# OpenBook_Schematic.net
KiCad netlist of a schematic drawn in EAGLE
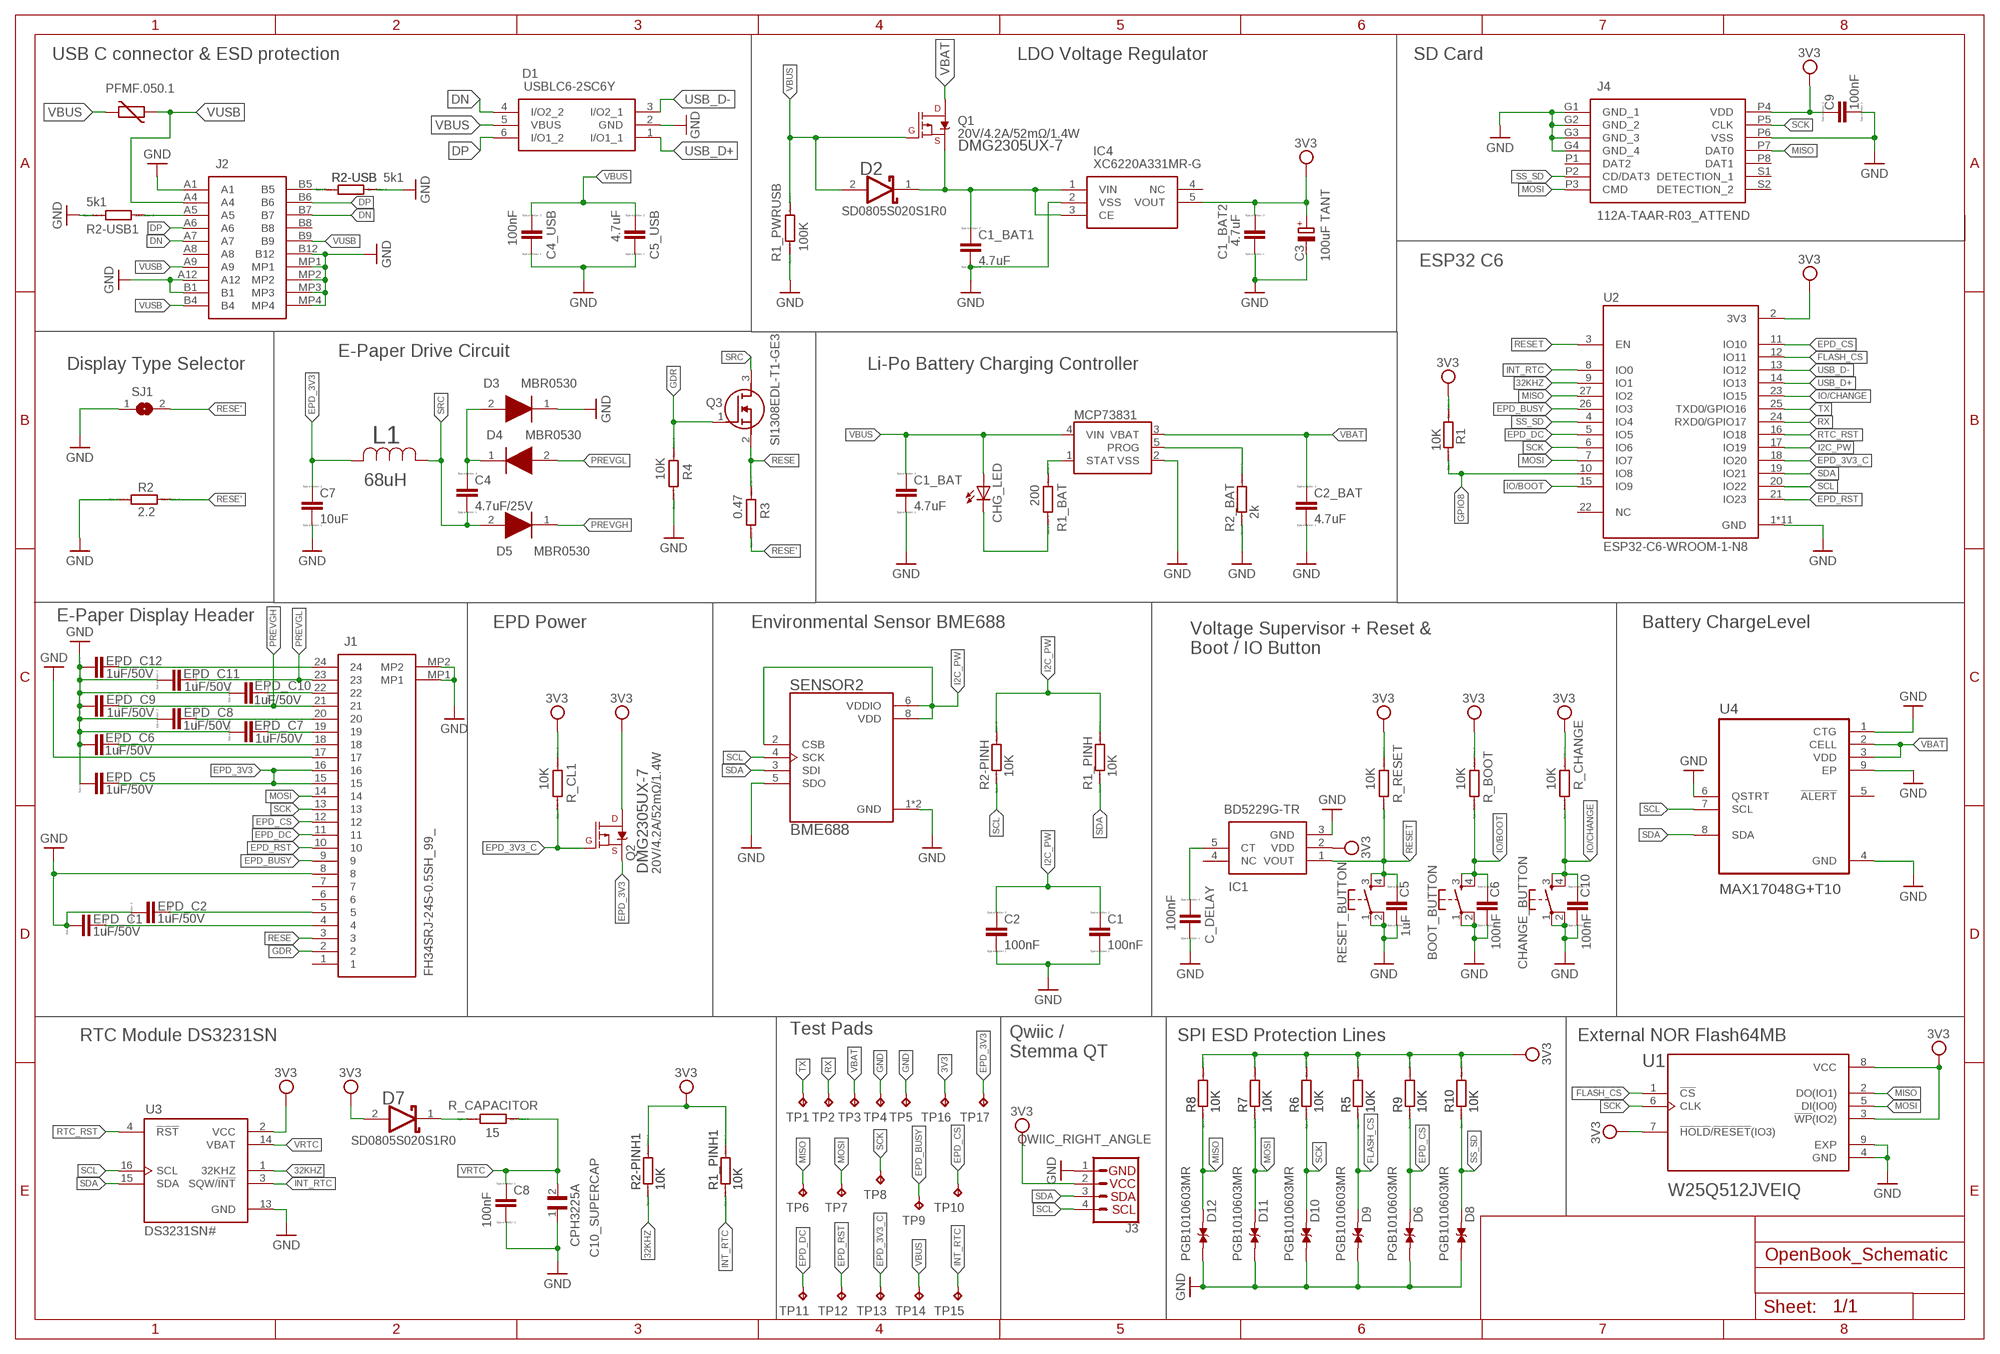
[diagram p0: schematic, sheet 1]

(export (version "E")
  (design (tool "Eeschema 10.0.6"))
  (components
    (comp (ref "BOOT_BUTTON")
      (value "BUTTON_CUSYOMV1")
      (footprint "eagle-import:MYBUTTON")
      (libsource (lib "eagle-import") (part "BUTTON_CUSYOMV1"))
    )
    (comp (ref "C1")
      (value "100nF")
      (footprint "eagle-import:EAGLE-LTSPICE_C0402")
      (libsource (lib "eagle-import") (part "EAGLE-LTSPICE_CC0402"))
    )
    (comp (ref "C1_BAT")
      (value "4.7uF")
      (footprint "eagle-import:EAGLE-LTSPICE_C0402")
      (libsource (lib "eagle-import") (part "EAGLE-LTSPICE_CC0402"))
    )
    (comp (ref "C1_BAT1")
      (value "4.7uF")
      (footprint "eagle-import:EAGLE-LTSPICE_C0402")
      (libsource (lib "eagle-import") (part "EAGLE-LTSPICE_CC0402"))
    )
    (comp (ref "C1_BAT2")
      (value "4.7uF")
      (footprint "eagle-import:EAGLE-LTSPICE_C0402")
      (libsource (lib "eagle-import") (part "EAGLE-LTSPICE_CC0402"))
    )
    (comp (ref "C2")
      (value "100nF")
      (footprint "eagle-import:EAGLE-LTSPICE_C0402")
      (libsource (lib "eagle-import") (part "EAGLE-LTSPICE_CC0402"))
    )
    (comp (ref "C2_BAT")
      (value "4.7uF")
      (footprint "eagle-import:EAGLE-LTSPICE_C0402")
      (libsource (lib "eagle-import") (part "EAGLE-LTSPICE_CC0402"))
    )
    (comp (ref "C3")
      (value "100uF TANT")
      (footprint "eagle-import:RCL_CT3528")
      (libsource (lib "eagle-import") (part "RCL_CPOL-EUCT3528"))
    )
    (comp (ref "C4")
      (value "4.7uF/25V")
      (footprint "eagle-import:EAGLE-LTSPICE_C0402")
      (libsource (lib "eagle-import") (part "EAGLE-LTSPICE_CC0402"))
    )
    (comp (ref "C4_USB")
      (value "100nF")
      (footprint "eagle-import:EAGLE-LTSPICE_C0402")
      (libsource (lib "eagle-import") (part "EAGLE-LTSPICE_CC0402"))
    )
    (comp (ref "C5")
      (value "1uF")
      (footprint "eagle-import:EAGLE-LTSPICE_C0402")
      (libsource (lib "eagle-import") (part "EAGLE-LTSPICE_CC0402"))
    )
    (comp (ref "C5_USB")
      (value "4.7uF")
      (footprint "eagle-import:EAGLE-LTSPICE_C0402")
      (libsource (lib "eagle-import") (part "EAGLE-LTSPICE_CC0402"))
    )
    (comp (ref "C6")
      (value "100nF")
      (footprint "eagle-import:EAGLE-LTSPICE_C0402")
      (libsource (lib "eagle-import") (part "EAGLE-LTSPICE_CC0402"))
    )
    (comp (ref "C7")
      (value "10uF")
      (footprint "eagle-import:EAGLE-LTSPICE_C0402")
      (libsource (lib "eagle-import") (part "EAGLE-LTSPICE_CC0402"))
    )
    (comp (ref "C8")
      (value "100nF")
      (footprint "eagle-import:EAGLE-LTSPICE_C0402")
      (libsource (lib "eagle-import") (part "EAGLE-LTSPICE_CC0402"))
    )
    (comp (ref "C9")
      (value "100nF")
      (footprint "eagle-import:EAGLE-LTSPICE_C0402")
      (libsource (lib "eagle-import") (part "EAGLE-LTSPICE_CC0402"))
    )
    (comp (ref "C10")
      (value "100nF")
      (footprint "eagle-import:EAGLE-LTSPICE_C0402")
      (libsource (lib "eagle-import") (part "EAGLE-LTSPICE_CC0402"))
    )
    (comp (ref "C10_SUPERCAP")
      (value "CPH3225A")
      (footprint "eagle-import:CAPCP3225X100N")
      (fields (field (name "MF") "Seiko Instruments"))
      (libsource (lib "eagle-import") (part "CPH3225A"))
    )
    (comp (ref "CHANGE_BUTTON")
      (value "BUTTON_CUSYOMV1")
      (footprint "eagle-import:MYBUTTON")
      (libsource (lib "eagle-import") (part "BUTTON_CUSYOMV1"))
    )
    (comp (ref "CHG_LED")
      (value "ADAFRUIT_LEDCHIP-LED0603")
      (footprint "eagle-import:ADAFRUIT_CHIP-LED0603")
      (libsource (lib "eagle-import") (part "ADAFRUIT_LEDCHIP-LED0603"))
    )
    (comp (ref "C_DELAY")
      (value "100nF")
      (footprint "eagle-import:EAGLE-LTSPICE_C0402")
      (libsource (lib "eagle-import") (part "EAGLE-LTSPICE_CC0402"))
    )
    (comp (ref "D1")
      (value "USBLC6-2SC6Y")
      (footprint "eagle-import:SOT95P280X145-6N")
      (fields (field (name "MF") "STMicroelectronics"))
      (libsource (lib "eagle-import") (part "USBLC6-2SC6Y"))
    )
    (comp (ref "D2")
      (value "ESP32_WROVER_AVX---SD0805S020S1R0_AVX_SD0805S020S1R0_0_0AVX_SD0805S020S1R0_0_0")
      (footprint "eagle-import:ESP32_WROVER_AVX---SD0805S020S1R0_AVX_SD0805S020S1R0_0")
      (fields
        (field (name "DIGIKEY_PART_NUMBER") "478-7800-1-ND")
        (field (name "MF") "AVX")
        (field (name "MOUSER_PART_NUMBER") "581-SD0805S020S1R0")
        (field (name "SD0805S020S1R0") "SD0805S020S1R0")
      )
      (libsource (lib "eagle-import") (part "ESP32_WROVER_AVX---SD0805S020S1R0_AVX_SD0805S020S1R0_0_0AVX_SD0805S020S1R0_0_0"))
    )
    (comp (ref "D3")
      (value "MBR0530")
      (footprint "eagle-import:SOD3716X135N")
      (fields (field (name "MF") "ON Semiconductor"))
      (libsource (lib "eagle-import") (part "MBR0530"))
    )
    (comp (ref "D4")
      (value "MBR0530")
      (footprint "eagle-import:SOD3716X135N")
      (fields (field (name "MF") "ON Semiconductor"))
      (libsource (lib "eagle-import") (part "MBR0530"))
    )
    (comp (ref "D5")
      (value "MBR0530")
      (footprint "eagle-import:SOD3716X135N")
      (fields (field (name "MF") "ON Semiconductor"))
      (libsource (lib "eagle-import") (part "MBR0530"))
    )
    (comp (ref "D6")
      (value "PGB1010603MR")
      (footprint "eagle-import:DIOC1608X36N")
      (fields (field (name "MF") "Littelfuse Inc."))
      (libsource (lib "eagle-import") (part "PGB1010603MR"))
    )
    (comp (ref "D7")
      (value "ESP32_WROVER_AVX---SD0805S020S1R0_AVX_SD0805S020S1R0_0_0AVX_SD0805S020S1R0_0_0")
      (footprint "eagle-import:ESP32_WROVER_AVX---SD0805S020S1R0_AVX_SD0805S020S1R0_0")
      (fields
        (field (name "DIGIKEY_PART_NUMBER") "478-7800-1-ND")
        (field (name "MF") "AVX")
        (field (name "MOUSER_PART_NUMBER") "581-SD0805S020S1R0")
        (field (name "DIODE") "SD0805S020S1R0")
      )
      (libsource (lib "eagle-import") (part "ESP32_WROVER_AVX---SD0805S020S1R0_AVX_SD0805S020S1R0_0_0AVX_SD0805S020S1R0_0_0"))
    )
    (comp (ref "D8")
      (value "PGB1010603MR")
      (footprint "eagle-import:DIOC1608X36N")
      (fields (field (name "MF") "Littelfuse Inc."))
      (libsource (lib "eagle-import") (part "PGB1010603MR"))
    )
    (comp (ref "D9")
      (value "PGB1010603MR")
      (footprint "eagle-import:DIOC1608X36N")
      (fields (field (name "MF") "Littelfuse Inc."))
      (libsource (lib "eagle-import") (part "PGB1010603MR"))
    )
    (comp (ref "D10")
      (value "PGB1010603MR")
      (footprint "eagle-import:DIOC1608X36N")
      (fields (field (name "MF") "Littelfuse Inc."))
      (libsource (lib "eagle-import") (part "PGB1010603MR"))
    )
    (comp (ref "D11")
      (value "PGB1010603MR")
      (footprint "eagle-import:DIOC1608X36N")
      (fields (field (name "MF") "Littelfuse Inc."))
      (libsource (lib "eagle-import") (part "PGB1010603MR"))
    )
    (comp (ref "D12")
      (value "PGB1010603MR")
      (footprint "eagle-import:DIOC1608X36N")
      (fields (field (name "MF") "Littelfuse Inc."))
      (libsource (lib "eagle-import") (part "PGB1010603MR"))
    )
    (comp (ref "EPD_C1")
      (value "1uF/50V")
      (footprint "eagle-import:EAGLE-LTSPICE_C0402")
      (libsource (lib "eagle-import") (part "EAGLE-LTSPICE_CC0402"))
    )
    (comp (ref "EPD_C2")
      (value "1uF/50V")
      (footprint "eagle-import:EAGLE-LTSPICE_C0402")
      (libsource (lib "eagle-import") (part "EAGLE-LTSPICE_CC0402"))
    )
    (comp (ref "EPD_C5")
      (value "1uF/50V")
      (footprint "eagle-import:EAGLE-LTSPICE_C0402")
      (libsource (lib "eagle-import") (part "EAGLE-LTSPICE_CC0402"))
    )
    (comp (ref "EPD_C6")
      (value "1uF/50V")
      (footprint "eagle-import:EAGLE-LTSPICE_C0402")
      (libsource (lib "eagle-import") (part "EAGLE-LTSPICE_CC0402"))
    )
    (comp (ref "EPD_C7")
      (value "1uF/50V")
      (footprint "eagle-import:EAGLE-LTSPICE_C0402")
      (libsource (lib "eagle-import") (part "EAGLE-LTSPICE_CC0402"))
    )
    (comp (ref "EPD_C8")
      (value "1uF/50V")
      (footprint "eagle-import:EAGLE-LTSPICE_C0402")
      (libsource (lib "eagle-import") (part "EAGLE-LTSPICE_CC0402"))
    )
    (comp (ref "EPD_C9")
      (value "1uF/50V")
      (footprint "eagle-import:EAGLE-LTSPICE_C0402")
      (libsource (lib "eagle-import") (part "EAGLE-LTSPICE_CC0402"))
    )
    (comp (ref "EPD_C10")
      (value "1uF/50V")
      (footprint "eagle-import:EAGLE-LTSPICE_C0402")
      (libsource (lib "eagle-import") (part "EAGLE-LTSPICE_CC0402"))
    )
    (comp (ref "EPD_C11")
      (value "1uF/50V")
      (footprint "eagle-import:EAGLE-LTSPICE_C0402")
      (libsource (lib "eagle-import") (part "EAGLE-LTSPICE_CC0402"))
    )
    (comp (ref "EPD_C12")
      (value "1uF/50V")
      (footprint "eagle-import:EAGLE-LTSPICE_C0402")
      (libsource (lib "eagle-import") (part "EAGLE-LTSPICE_CC0402"))
    )
    (comp (ref "IC1")
      (value "BD5229G-TR")
      (footprint "eagle-import:SOT95P280X125-5N")
      (fields (field (name "MOUSER_PART_NUMBER") "755-BD5229G-TR"))
      (libsource (lib "eagle-import") (part "BD5229G-TR"))
    )
    (comp (ref "IC4")
      (value "XC6220A331MR-G")
      (footprint "eagle-import:SOT95P280X120-5N")
      (fields (field (name "MOUSER_PART_NUMBER") "865-XC6220A331MR-G"))
      (libsource (lib "eagle-import") (part "XC6220A331MR-G"))
    )
    (comp (ref "J1")
      (value "FH34SRJ-24S-0.5SH_99_")
      (footprint "eagle-import:FH34SRJ24S05SH99")
      (fields
        (field (name "MANUFACTURER_PART_NUMBER") "FH34SRJ-24S-0.5SH(99)")
        (field (name "MOUSER_PART_NUMBER") "798-FH34SRJ24S05SH99")
      )
      (libsource (lib "eagle-import") (part "FH34SRJ-24S-0.5SH_99_"))
    )
    (comp (ref "J2")
      (value "SAMACSYS_PARTS_USB4110-GF-A")
      (footprint "eagle-import:SAMACSYS_PARTS_USB4110GFA")
      (fields
        (field (name "MANUFACTURER_PART_NUMBER") "USB4110-GF-A")
        (field (name "MOUSER_PART_NUMBER") "640-USB4110-GF-A")
      )
      (libsource (lib "eagle-import") (part "SAMACSYS_PARTS_USB4110-GF-A"))
    )
    (comp (ref "J3")
      (value "QWIIC_RIGHT_ANGLE")
      (footprint "eagle-import:JST04_1MM_RA")
      (libsource (lib "eagle-import") (part "QWIIC_CONNECTORJS-1MM"))
    )
    (comp (ref "J4")
      (value "112A-TAAR-R03_ATTEND")
      (footprint "eagle-import:112ATAARR03ATTEND")
      (fields (field (name "MANUFACTURER_PART_NUMBER") "112A-TAAR-R03 ATTEND"))
      (libsource (lib "eagle-import") (part "112A-TAAR-R03_ATTEND"))
    )
    (comp (ref "L1")
      (value "744043680IND_4828-WE-TPC_WRE")
      (footprint "eagle-import:IND_4828-WE-TPC_WRE")
      (fields
        (field (name "MANUFACTURER_PART_NUMBER") "744043680")
        (field (name "L1") "68uH")
        (field (name "COPYRIGHT") "Copyright (C) 2024 Ultra Librarian. All rights reserved.")
      )
      (libsource (lib "eagle-import") (part "744043680IND_4828-WE-TPC_WRE"))
    )
    (comp (ref "MCP73831")
      (value "ESP32_WROVER_SPARKFUN-IC-POWER_MCP73831")
      (footprint "eagle-import:ESP32_WROVER_SPARKFUN-IC-POWER_SOT23-5")
      (libsource (lib "eagle-import") (part "ESP32_WROVER_SPARKFUN-IC-POWER_MCP73831"))
    )
    (comp (ref "PFMF.050.1")
      (value "ESP32C6_VARISTORCN1812")
      (footprint "eagle-import:ESP32C6_VARISTOR_CT_CN1812")
      (libsource (lib "eagle-import") (part "ESP32C6_VARISTORCN1812"))
    )
    (comp (ref "Q1")
      (value "20V/4.2A/52mΩ/1.4W")
      (footprint "eagle-import:ESP32_WROVER_SPARKFUN-DISCRETESEMI_SOT23-3")
      (libsource (lib "eagle-import") (part "ESP32_WROVER_SPARKFUN-DISCRETESEMI_MOSFET_PCH-DMG2305UX-7"))
    )
    (comp (ref "Q2")
      (value "20V/4.2A/52mΩ/1.4W")
      (footprint "eagle-import:ESP32_WROVER_SPARKFUN-DISCRETESEMI_SOT23-3")
      (libsource (lib "eagle-import") (part "ESP32_WROVER_SPARKFUN-DISCRETESEMI_MOSFET_PCH-DMG2305UX-7"))
    )
    (comp (ref "Q3")
      (value "SI1308EDL-T1-GE3")
      (footprint "eagle-import:SOT65P210X110-3N")
      (fields (field (name "MF") "Vishay Siliconix"))
      (libsource (lib "eagle-import") (part "SI1308EDL-T1-GE3"))
    )
    (comp (ref "R1")
      (value "10K")
      (footprint "eagle-import:ESP32_WROVER_EAGLE-LTSPICE_R0402")
      (libsource (lib "eagle-import") (part "ESP32_WROVER_EAGLE-LTSPICE_RR0402"))
    )
    (comp (ref "R1_BAT")
      (value "200")
      (footprint "eagle-import:ESP32_WROVER_EAGLE-LTSPICE_R0402")
      (libsource (lib "eagle-import") (part "ESP32_WROVER_EAGLE-LTSPICE_RR0402"))
    )
    (comp (ref "R1_PINH")
      (value "10K")
      (footprint "eagle-import:ESP32_WROVER_EAGLE-LTSPICE_R0402")
      (libsource (lib "eagle-import") (part "ESP32_WROVER_EAGLE-LTSPICE_RR0402"))
    )
    (comp (ref "R1_PINH1")
      (value "10K")
      (footprint "eagle-import:ESP32_WROVER_EAGLE-LTSPICE_R0402")
      (libsource (lib "eagle-import") (part "ESP32_WROVER_EAGLE-LTSPICE_RR0402"))
    )
    (comp (ref "R1_PWRUSB")
      (value "100K")
      (footprint "eagle-import:ESP32_WROVER_EAGLE-LTSPICE_R0402")
      (libsource (lib "eagle-import") (part "ESP32_WROVER_EAGLE-LTSPICE_RR0402"))
    )
    (comp (ref "R2")
      (value "2.2")
      (footprint "eagle-import:ESP32_WROVER_EAGLE-LTSPICE_R0402")
      (libsource (lib "eagle-import") (part "ESP32_WROVER_EAGLE-LTSPICE_RR0402"))
    )
    (comp (ref "R2-PINH")
      (value "10K")
      (footprint "eagle-import:ESP32_WROVER_EAGLE-LTSPICE_R0402")
      (libsource (lib "eagle-import") (part "ESP32_WROVER_EAGLE-LTSPICE_RR0402"))
    )
    (comp (ref "R2-PINH1")
      (value "10K")
      (footprint "eagle-import:ESP32_WROVER_EAGLE-LTSPICE_R0402")
      (libsource (lib "eagle-import") (part "ESP32_WROVER_EAGLE-LTSPICE_RR0402"))
    )
    (comp (ref "R2-USB")
      (value "5k1")
      (footprint "eagle-import:ESP32_WROVER_EAGLE-LTSPICE_R0402")
      (libsource (lib "eagle-import") (part "ESP32_WROVER_EAGLE-LTSPICE_RR0402"))
    )
    (comp (ref "R2-USB1")
      (value "5k1")
      (footprint "eagle-import:ESP32_WROVER_EAGLE-LTSPICE_R0402")
      (libsource (lib "eagle-import") (part "ESP32_WROVER_EAGLE-LTSPICE_RR0402"))
    )
    (comp (ref "R2_BAT")
      (value "2k")
      (footprint "eagle-import:ESP32_WROVER_EAGLE-LTSPICE_R0402")
      (libsource (lib "eagle-import") (part "ESP32_WROVER_EAGLE-LTSPICE_RR0402"))
    )
    (comp (ref "R3")
      (value "0.47")
      (footprint "eagle-import:ESP32_WROVER_EAGLE-LTSPICE_R0402")
      (libsource (lib "eagle-import") (part "ESP32_WROVER_EAGLE-LTSPICE_RR0402"))
    )
    (comp (ref "R4")
      (value "10K")
      (footprint "eagle-import:ESP32_WROVER_EAGLE-LTSPICE_R0402")
      (libsource (lib "eagle-import") (part "ESP32_WROVER_EAGLE-LTSPICE_RR0402"))
    )
    (comp (ref "R5")
      (value "10K")
      (footprint "eagle-import:ESP32_WROVER_EAGLE-LTSPICE_R0402")
      (libsource (lib "eagle-import") (part "ESP32_WROVER_EAGLE-LTSPICE_RR0402"))
    )
    (comp (ref "R6")
      (value "10K")
      (footprint "eagle-import:ESP32_WROVER_EAGLE-LTSPICE_R0402")
      (libsource (lib "eagle-import") (part "ESP32_WROVER_EAGLE-LTSPICE_RR0402"))
    )
    (comp (ref "R7")
      (value "10K")
      (footprint "eagle-import:ESP32_WROVER_EAGLE-LTSPICE_R0402")
      (libsource (lib "eagle-import") (part "ESP32_WROVER_EAGLE-LTSPICE_RR0402"))
    )
    (comp (ref "R8")
      (value "10K")
      (footprint "eagle-import:ESP32_WROVER_EAGLE-LTSPICE_R0402")
      (libsource (lib "eagle-import") (part "ESP32_WROVER_EAGLE-LTSPICE_RR0402"))
    )
    (comp (ref "R9")
      (value "10K")
      (footprint "eagle-import:ESP32_WROVER_EAGLE-LTSPICE_R0402")
      (libsource (lib "eagle-import") (part "ESP32_WROVER_EAGLE-LTSPICE_RR0402"))
    )
    (comp (ref "R10")
      (value "10K")
      (footprint "eagle-import:ESP32_WROVER_EAGLE-LTSPICE_R0402")
      (libsource (lib "eagle-import") (part "ESP32_WROVER_EAGLE-LTSPICE_RR0402"))
    )
    (comp (ref "RESET_BUTTON")
      (value "BUTTON_CUSYOMV1")
      (footprint "eagle-import:MYBUTTON")
      (libsource (lib "eagle-import") (part "BUTTON_CUSYOMV1"))
    )
    (comp (ref "R_BOOT")
      (value "10K")
      (footprint "eagle-import:ESP32_WROVER_EAGLE-LTSPICE_R0402")
      (libsource (lib "eagle-import") (part "ESP32_WROVER_EAGLE-LTSPICE_RR0402"))
    )
    (comp (ref "R_CAPACITOR")
      (value "15")
      (footprint "eagle-import:ESP32_WROVER_EAGLE-LTSPICE_R0402")
      (libsource (lib "eagle-import") (part "ESP32_WROVER_EAGLE-LTSPICE_RR0402"))
    )
    (comp (ref "R_CHANGE")
      (value "10K")
      (footprint "eagle-import:ESP32_WROVER_EAGLE-LTSPICE_R0402")
      (libsource (lib "eagle-import") (part "ESP32_WROVER_EAGLE-LTSPICE_RR0402"))
    )
    (comp (ref "R_CL1")
      (value "10K")
      (footprint "eagle-import:ESP32_WROVER_EAGLE-LTSPICE_R0402")
      (libsource (lib "eagle-import") (part "ESP32_WROVER_EAGLE-LTSPICE_RR0402"))
    )
    (comp (ref "R_RESET")
      (value "10K")
      (footprint "eagle-import:ESP32_WROVER_EAGLE-LTSPICE_R0402")
      (libsource (lib "eagle-import") (part "ESP32_WROVER_EAGLE-LTSPICE_RR0402"))
    )
    (comp (ref "SENSOR2")
      (value "ESP32_WROVER_BME680_BME680")
      (footprint "eagle-import:ESP32_WROVER_BME680_PSON80P300X300X100-8N")
      (fields
        (field (name "MF") "Bosch Sensortec")
        (field (name "MP") "BME680")
        (field (name "MP1") "BME688")
      )
      (libsource (lib "eagle-import") (part "ESP32_WROVER_BME680_BME680"))
    )
    (comp (ref "SJ1") (value "SJ") (footprint "eagle-import:SJ") (libsource (lib "eagle-import") (part "SJ")))
    (comp (ref "TP1")
      (value "TPTP20R")
      (footprint "eagle-import:TP20R")
      (libsource (lib "eagle-import") (part "TPTP20R"))
    )
    (comp (ref "TP2")
      (value "TPTP20R")
      (footprint "eagle-import:TP20R")
      (libsource (lib "eagle-import") (part "TPTP20R"))
    )
    (comp (ref "TP3")
      (value "TPTP20R")
      (footprint "eagle-import:TP20R")
      (libsource (lib "eagle-import") (part "TPTP20R"))
    )
    (comp (ref "TP4")
      (value "TPTP20R")
      (footprint "eagle-import:TP20R")
      (libsource (lib "eagle-import") (part "TPTP20R"))
    )
    (comp (ref "TP5")
      (value "TPTP20R")
      (footprint "eagle-import:TP20R")
      (libsource (lib "eagle-import") (part "TPTP20R"))
    )
    (comp (ref "TP6")
      (value "TPTP20R")
      (footprint "eagle-import:TP20R")
      (libsource (lib "eagle-import") (part "TPTP20R"))
    )
    (comp (ref "TP7")
      (value "TPTP20R")
      (footprint "eagle-import:TP20R")
      (libsource (lib "eagle-import") (part "TPTP20R"))
    )
    (comp (ref "TP8")
      (value "TPTP20R")
      (footprint "eagle-import:TP20R")
      (libsource (lib "eagle-import") (part "TPTP20R"))
    )
    (comp (ref "TP9")
      (value "TPTP20R")
      (footprint "eagle-import:TP20R")
      (libsource (lib "eagle-import") (part "TPTP20R"))
    )
    (comp (ref "TP10")
      (value "TPTP20R")
      (footprint "eagle-import:TP20R")
      (libsource (lib "eagle-import") (part "TPTP20R"))
    )
    (comp (ref "TP11")
      (value "TPTP20R")
      (footprint "eagle-import:TP20R")
      (libsource (lib "eagle-import") (part "TPTP20R"))
    )
    (comp (ref "TP12")
      (value "TPTP20R")
      (footprint "eagle-import:TP20R")
      (libsource (lib "eagle-import") (part "TPTP20R"))
    )
    (comp (ref "TP13")
      (value "TPTP20R")
      (footprint "eagle-import:TP20R")
      (libsource (lib "eagle-import") (part "TPTP20R"))
    )
    (comp (ref "TP14")
      (value "TPTP20R")
      (footprint "eagle-import:TP20R")
      (libsource (lib "eagle-import") (part "TPTP20R"))
    )
    (comp (ref "TP15")
      (value "TPTP20R")
      (footprint "eagle-import:TP20R")
      (libsource (lib "eagle-import") (part "TPTP20R"))
    )
    (comp (ref "TP16")
      (value "TPTP20R")
      (footprint "eagle-import:TP20R")
      (libsource (lib "eagle-import") (part "TPTP20R"))
    )
    (comp (ref "TP17")
      (value "TPTP20R")
      (footprint "eagle-import:TP20R")
      (libsource (lib "eagle-import") (part "TPTP20R"))
    )
    (comp (ref "U1")
      (value "W25Q512JVEIQ")
      (footprint "eagle-import:SON127P600X800X80-9N")
      (fields (field (name "MF") "Winbond Electronics"))
      (libsource (lib "eagle-import") (part "W25Q512JVEIQ"))
    )
    (comp (ref "U2")
      (value "ESP32-C6-WROOM-1-N8")
      (footprint "eagle-import:XCVR_ESP32-C6-WROOM-1-N8")
      (fields (field (name "MF") "Espressif Systems"))
      (libsource (lib "eagle-import") (part "ESP32-C6-WROOM-1-N8"))
    )
    (comp (ref "U3")
      (value "DS3231SN#")
      (footprint "eagle-import:SOIC127P1032X265-16N")
      (fields (field (name "MF") "Analog Devices"))
      (libsource (lib "eagle-import") (part "DS3231SN#"))
    )
    (comp (ref "U4")
      (value "MAX17048G+T10")
      (footprint "eagle-import:SON50P200X200X80-9N")
      (fields (field (name "MF") "Analog Devices"))
      (libsource (lib "eagle-import") (part "MAX17048G+T10"))
    )
  )
  (nets
    (net (code "1") (name "3V3") (class "Default")
      (node (ref "C1_BAT2") (pin "2") (pinfunction "2_2") (pintype "passive"))
      (node (ref "C3") (pin "+") (pinfunction "+_+") (pintype "passive"))
      (node (ref "C9") (pin "2") (pinfunction "2_2") (pintype "passive"))
      (node (ref "D7") (pin "2") (pinfunction "ANODE_2") (pintype "bidirectional"))
      (node (ref "IC1") (pin "2") (pinfunction "VDD_2") (pintype "bidirectional"))
      (node (ref "IC4") (pin "5") (pinfunction "VOUT_5") (pintype "bidirectional"))
      (node (ref "J3") (pin "2") (pinfunction "2_2") (pintype "power_in"))
      (node (ref "J4") (pin "P4") (pinfunction "VDD_P4") (pintype "bidirectional"))
      (node (ref "Q2") (pin "3") (pinfunction "D_3") (pintype "bidirectional"))
      (node (ref "R1") (pin "1") (pinfunction "1_1") (pintype "passive"))
      (node (ref "R10") (pin "2") (pinfunction "2_2") (pintype "passive"))
      (node (ref "R1_PINH1") (pin "2") (pinfunction "2_2") (pintype "passive"))
      (node (ref "R2-PINH1") (pin "2") (pinfunction "2_2") (pintype "passive"))
      (node (ref "R5") (pin "2") (pinfunction "2_2") (pintype "passive"))
      (node (ref "R6") (pin "2") (pinfunction "2_2") (pintype "passive"))
      (node (ref "R7") (pin "2") (pinfunction "2_2") (pintype "passive"))
      (node (ref "R8") (pin "2") (pinfunction "2_2") (pintype "passive"))
      (node (ref "R9") (pin "2") (pinfunction "2_2") (pintype "passive"))
      (node (ref "R_BOOT") (pin "2") (pinfunction "2_2") (pintype "passive"))
      (node (ref "R_CHANGE") (pin "2") (pinfunction "2_2") (pintype "passive"))
      (node (ref "R_CL1") (pin "2") (pinfunction "2_2") (pintype "passive"))
      (node (ref "R_RESET") (pin "2") (pinfunction "2_2") (pintype "passive"))
      (node (ref "TP16") (pin "TP") (pinfunction "TP_TP") (pintype "input"))
      (node (ref "U1") (pin "3") (pinfunction "~{WP}(IO2)_3") (pintype "bidirectional"))
      (node (ref "U1") (pin "7") (pinfunction "~{HOLD}/~{RESET}(IO3)_7") (pintype "bidirectional"))
      (node (ref "U1") (pin "8") (pinfunction "VCC_8") (pintype "power_in"))
      (node (ref "U2") (pin "2") (pinfunction "3V3_2") (pintype "power_in"))
      (node (ref "U3") (pin "2") (pinfunction "VCC_2") (pintype "power_in"))
    )
    (net (code "2") (name "32KHZ") (class "Default")
      (node (ref "R2-PINH1") (pin "1") (pinfunction "1_1") (pintype "passive"))
      (node (ref "U2") (pin "9") (pinfunction "IO1_9") (pintype "bidirectional"))
      (node (ref "U3") (pin "1") (pinfunction "32KHZ_1") (pintype "output"))
    )
    (net (code "3") (name "DN") (class "Default")
      (node (ref "D1") (pin "4") (pinfunction "I/O2_2_4") (pintype "bidirectional"))
      (node (ref "J2") (pin "A7") (pinfunction "A7_A7") (pintype "bidirectional"))
      (node (ref "J2") (pin "B7") (pinfunction "B7_B7") (pintype "bidirectional"))
    )
    (net (code "4") (name "DP") (class "Default")
      (node (ref "D1") (pin "6") (pinfunction "I/O1_2_6") (pintype "bidirectional"))
      (node (ref "J2") (pin "A6") (pinfunction "A6_A6") (pintype "bidirectional"))
      (node (ref "J2") (pin "B6") (pinfunction "B6_B6") (pintype "bidirectional"))
    )
    (net (code "5") (name "EPD_3V3") (class "Default")
      (node (ref "C7") (pin "2") (pinfunction "2_2") (pintype "passive"))
      (node (ref "EPD_C5") (pin "1") (pinfunction "1_1") (pintype "passive"))
      (node (ref "J1") (pin "15") (pinfunction "15_15") (pintype "bidirectional"))
      (node (ref "J1") (pin "16") (pinfunction "16_16") (pintype "bidirectional"))
      (node (ref "L1") (pin "2") (pinfunction "2_2") (pintype "passive"))
      (node (ref "Q2") (pin "2") (pinfunction "S_2") (pintype "bidirectional"))
      (node (ref "TP17") (pin "TP") (pinfunction "TP_TP") (pintype "input"))
    )
    (net (code "6") (name "EPD_3V3_C") (class "Default")
      (node (ref "Q2") (pin "1") (pinfunction "G_1") (pintype "bidirectional"))
      (node (ref "R_CL1") (pin "1") (pinfunction "1_1") (pintype "passive"))
      (node (ref "TP13") (pin "TP") (pinfunction "TP_TP") (pintype "input"))
      (node (ref "U2") (pin "18") (pinfunction "IO20_18") (pintype "bidirectional"))
    )
    (net (code "7") (name "EPD_BUSY") (class "Default")
      (node (ref "J1") (pin "9") (pinfunction "9_9") (pintype "bidirectional"))
      (node (ref "TP9") (pin "TP") (pinfunction "TP_TP") (pintype "input"))
      (node (ref "U2") (pin "26") (pinfunction "IO3_26") (pintype "bidirectional"))
    )
    (net (code "8") (name "EPD_CS") (class "Default")
      (node (ref "D6") (pin "2") (pinfunction "2_2") (pintype "passive"))
      (node (ref "J1") (pin "12") (pinfunction "12_12") (pintype "bidirectional"))
      (node (ref "R9") (pin "1") (pinfunction "1_1") (pintype "passive"))
      (node (ref "TP10") (pin "TP") (pinfunction "TP_TP") (pintype "input"))
      (node (ref "U2") (pin "11") (pinfunction "IO10_11") (pintype "bidirectional"))
    )
    (net (code "9") (name "EPD_DC") (class "Default")
      (node (ref "J1") (pin "11") (pinfunction "11_11") (pintype "bidirectional"))
      (node (ref "TP11") (pin "TP") (pinfunction "TP_TP") (pintype "input"))
      (node (ref "U2") (pin "5") (pinfunction "IO5_5") (pintype "bidirectional"))
    )
    (net (code "10") (name "EPD_RST") (class "Default")
      (node (ref "J1") (pin "10") (pinfunction "10_10") (pintype "bidirectional"))
      (node (ref "TP12") (pin "TP") (pinfunction "TP_TP") (pintype "input"))
      (node (ref "U2") (pin "21") (pinfunction "IO23_21") (pintype "bidirectional"))
    )
    (net (code "11") (name "FLASH_CS") (class "Default")
      (node (ref "D9") (pin "2") (pinfunction "2_2") (pintype "passive"))
      (node (ref "R5") (pin "1") (pinfunction "1_1") (pintype "passive"))
      (node (ref "U1") (pin "1") (pinfunction "~{CS}_1") (pintype "input"))
      (node (ref "U2") (pin "12") (pinfunction "IO11_12") (pintype "bidirectional"))
    )
    (net (code "12") (name "GDR") (class "Default")
      (node (ref "J1") (pin "2") (pinfunction "2_2") (pintype "bidirectional"))
      (node (ref "Q3") (pin "1") (pinfunction "G_1") (pintype "bidirectional"))
      (node (ref "R4") (pin "2") (pinfunction "2_2") (pintype "passive"))
    )
    (net (code "13") (name "GND") (class "Default")
      (node (ref "BOOT_BUTTON") (pin "1") (pinfunction "1_1") (pintype "passive"))
      (node (ref "BOOT_BUTTON") (pin "2") (pinfunction "2_2") (pintype "passive"))
      (node (ref "C1") (pin "1") (pinfunction "1_1") (pintype "passive"))
      (node (ref "C10") (pin "1") (pinfunction "1_1") (pintype "passive"))
      (node (ref "C10_SUPERCAP") (pin "1") (pinfunction "1_1") (pintype "passive"))
      (node (ref "C1_BAT") (pin "1") (pinfunction "1_1") (pintype "passive"))
      (node (ref "C1_BAT1") (pin "1") (pinfunction "1_1") (pintype "passive"))
      (node (ref "C1_BAT2") (pin "1") (pinfunction "1_1") (pintype "passive"))
      (node (ref "C2") (pin "1") (pinfunction "1_1") (pintype "passive"))
      (node (ref "C2_BAT") (pin "1") (pinfunction "1_1") (pintype "passive"))
      (node (ref "C3") (pin "-") (pinfunction "-_-") (pintype "passive"))
      (node (ref "C4_USB") (pin "1") (pinfunction "1_1") (pintype "passive"))
      (node (ref "C5") (pin "1") (pinfunction "1_1") (pintype "passive"))
      (node (ref "C5_USB") (pin "1") (pinfunction "1_1") (pintype "passive"))
      (node (ref "C6") (pin "1") (pinfunction "1_1") (pintype "passive"))
      (node (ref "C7") (pin "1") (pinfunction "1_1") (pintype "passive"))
      (node (ref "C8") (pin "2") (pinfunction "2_2") (pintype "passive"))
      (node (ref "C9") (pin "1") (pinfunction "1_1") (pintype "passive"))
      (node (ref "CHANGE_BUTTON") (pin "1") (pinfunction "1_1") (pintype "passive"))
      (node (ref "CHANGE_BUTTON") (pin "2") (pinfunction "2_2") (pintype "passive"))
      (node (ref "C_DELAY") (pin "1") (pinfunction "1_1") (pintype "passive"))
      (node (ref "D1") (pin "2") (pinfunction "GND_2") (pintype "bidirectional"))
      (node (ref "D10") (pin "1") (pinfunction "1_1") (pintype "passive"))
      (node (ref "D11") (pin "1") (pinfunction "1_1") (pintype "passive"))
      (node (ref "D12") (pin "1") (pinfunction "1_1") (pintype "passive"))
      (node (ref "D3") (pin "1") (pinfunction "K_1") (pintype "bidirectional"))
      (node (ref "D6") (pin "1") (pinfunction "1_1") (pintype "passive"))
      (node (ref "D8") (pin "1") (pinfunction "1_1") (pintype "passive"))
      (node (ref "D9") (pin "1") (pinfunction "1_1") (pintype "passive"))
      (node (ref "EPD_C1") (pin "2") (pinfunction "2_2") (pintype "passive"))
      (node (ref "EPD_C10") (pin "2") (pinfunction "2_2") (pintype "passive"))
      (node (ref "EPD_C11") (pin "2") (pinfunction "2_2") (pintype "passive"))
      (node (ref "EPD_C12") (pin "2") (pinfunction "2_2") (pintype "passive"))
      (node (ref "EPD_C2") (pin "2") (pinfunction "2_2") (pintype "passive"))
      (node (ref "EPD_C5") (pin "2") (pinfunction "2_2") (pintype "passive"))
      (node (ref "EPD_C6") (pin "2") (pinfunction "2_2") (pintype "passive"))
      (node (ref "EPD_C7") (pin "2") (pinfunction "2_2") (pintype "passive"))
      (node (ref "EPD_C8") (pin "2") (pinfunction "2_2") (pintype "passive"))
      (node (ref "EPD_C9") (pin "2") (pinfunction "2_2") (pintype "passive"))
      (node (ref "IC1") (pin "3") (pinfunction "GND_3") (pintype "bidirectional"))
      (node (ref "IC4") (pin "2") (pinfunction "VSS_2") (pintype "bidirectional"))
      (node (ref "J1") (pin "17") (pinfunction "17_17") (pintype "bidirectional"))
      (node (ref "J1") (pin "8") (pinfunction "8_8") (pintype "bidirectional"))
      (node (ref "J1") (pin "MP1") (pinfunction "MP1_MP1") (pintype "bidirectional"))
      (node (ref "J1") (pin "MP2") (pinfunction "MP2_MP2") (pintype "bidirectional"))
      (node (ref "J2") (pin "A1") (pinfunction "A1_A1") (pintype "bidirectional"))
      (node (ref "J2") (pin "A12") (pinfunction "A12_A12") (pintype "bidirectional"))
      (node (ref "J2") (pin "B1") (pinfunction "B1_B1") (pintype "bidirectional"))
      (node (ref "J2") (pin "B12") (pinfunction "B12_B12") (pintype "bidirectional"))
      (node (ref "J2") (pin "MP1") (pinfunction "MP1_MP1") (pintype "bidirectional"))
      (node (ref "J2") (pin "MP2") (pinfunction "MP2_MP2") (pintype "bidirectional"))
      (node (ref "J2") (pin "MP3") (pinfunction "MP3_MP3") (pintype "bidirectional"))
      (node (ref "J2") (pin "MP4") (pinfunction "MP4_MP4") (pintype "bidirectional"))
      (node (ref "J3") (pin "1") (pinfunction "1_1") (pintype "power_in"))
      (node (ref "J4") (pin "G1") (pinfunction "GND_1_G1") (pintype "bidirectional"))
      (node (ref "J4") (pin "G2") (pinfunction "GND_2_G2") (pintype "bidirectional"))
      (node (ref "J4") (pin "G3") (pinfunction "GND_3_G3") (pintype "bidirectional"))
      (node (ref "J4") (pin "G4") (pinfunction "GND_4_G4") (pintype "bidirectional"))
      (node (ref "J4") (pin "P6") (pinfunction "VSS_P6") (pintype "bidirectional"))
      (node (ref "MCP73831") (pin "2") (pinfunction "VSS_2") (pintype "power_in"))
      (node (ref "R1_PWRUSB") (pin "2") (pinfunction "2_2") (pintype "passive"))
      (node (ref "R2") (pin "1") (pinfunction "1_1") (pintype "passive"))
      (node (ref "R2-USB") (pin "2") (pinfunction "2_2") (pintype "passive"))
      (node (ref "R2-USB1") (pin "1") (pinfunction "1_1") (pintype "passive"))
      (node (ref "R2_BAT") (pin "1") (pinfunction "1_1") (pintype "passive"))
      (node (ref "R4") (pin "1") (pinfunction "1_1") (pintype "passive"))
      (node (ref "RESET_BUTTON") (pin "1") (pinfunction "1_1") (pintype "passive"))
      (node (ref "RESET_BUTTON") (pin "2") (pinfunction "2_2") (pintype "passive"))
      (node (ref "SENSOR2") (pin "1") (pinfunction "GND_1") (pintype "power_in"))
      (node (ref "SENSOR2") (pin "5") (pinfunction "SDO_5") (pintype "bidirectional"))
      (node (ref "SENSOR2") (pin "7") (pinfunction "GND_7") (pintype "power_in"))
      (node (ref "SJ1") (pin "1") (pinfunction "1_1") (pintype "passive"))
      (node (ref "TP4") (pin "TP") (pinfunction "TP_TP") (pintype "input"))
      (node (ref "TP5") (pin "TP") (pinfunction "TP_TP") (pintype "input"))
      (node (ref "U1") (pin "4") (pinfunction "GND_4") (pintype "power_in"))
      (node (ref "U1") (pin "9") (pinfunction "EXP_9") (pintype "passive"))
      (node (ref "U2") (pin "1") (pinfunction "GND_1") (pintype "power_in"))
      (node (ref "U2") (pin "28") (pinfunction "GND_28") (pintype "power_in"))
      (node (ref "U2") (pin "29_1") (pinfunction "GND_29_1") (pintype "power_in"))
      (node (ref "U2") (pin "29_2") (pinfunction "GND_29_2") (pintype "power_in"))
      (node (ref "U2") (pin "29_3") (pinfunction "GND_29_3") (pintype "power_in"))
      (node (ref "U2") (pin "29_4") (pinfunction "GND_29_4") (pintype "power_in"))
      (node (ref "U2") (pin "29_5") (pinfunction "GND_29_5") (pintype "power_in"))
      (node (ref "U2") (pin "29_6") (pinfunction "GND_29_6") (pintype "power_in"))
      (node (ref "U2") (pin "29_7") (pinfunction "GND_29_7") (pintype "power_in"))
      (node (ref "U2") (pin "29_8") (pinfunction "GND_29_8") (pintype "power_in"))
      (node (ref "U2") (pin "29_9") (pinfunction "GND_29_9") (pintype "power_in"))
      (node (ref "U3") (pin "13") (pinfunction "GND_13") (pintype "power_in"))
      (node (ref "U4") (pin "1") (pinfunction "CTG_1") (pintype "power_in"))
      (node (ref "U4") (pin "4") (pinfunction "GND_4") (pintype "power_in"))
      (node (ref "U4") (pin "6") (pinfunction "QSTRT_6") (pintype "input"))
      (node (ref "U4") (pin "9") (pinfunction "EP_9") (pintype "power_in"))
    )
    (net (code "14") (name "GPIO8") (class "Default")
      (node (ref "R1") (pin "2") (pinfunction "2_2") (pintype "passive"))
      (node (ref "U2") (pin "10") (pinfunction "IO8_10") (pintype "bidirectional"))
    )
    (net (code "15") (name "I2C_PW") (class "Default")
      (node (ref "C1") (pin "2") (pinfunction "2_2") (pintype "passive"))
      (node (ref "C2") (pin "2") (pinfunction "2_2") (pintype "passive"))
      (node (ref "R1_PINH") (pin "2") (pinfunction "2_2") (pintype "passive"))
      (node (ref "R2-PINH") (pin "2") (pinfunction "2_2") (pintype "passive"))
      (node (ref "SENSOR2") (pin "2") (pinfunction "CSB_2") (pintype "input"))
      (node (ref "SENSOR2") (pin "6") (pinfunction "VDDIO_6") (pintype "power_in"))
      (node (ref "SENSOR2") (pin "8") (pinfunction "VDD_8") (pintype "power_in"))
      (node (ref "U2") (pin "17") (pinfunction "IO19_17") (pintype "bidirectional"))
    )
    (net (code "16") (name "INT_RTC") (class "Default")
      (node (ref "R1_PINH1") (pin "1") (pinfunction "1_1") (pintype "passive"))
      (node (ref "TP15") (pin "TP") (pinfunction "TP_TP") (pintype "input"))
      (node (ref "U2") (pin "8") (pinfunction "IO0_8") (pintype "bidirectional"))
      (node (ref "U3") (pin "3") (pinfunction "SQW/~{INT}_3") (pintype "output"))
    )
    (net (code "17") (name "IO{slash}BOOT") (class "Default")
      (node (ref "BOOT_BUTTON") (pin "3") (pinfunction "3_3") (pintype "passive"))
      (node (ref "BOOT_BUTTON") (pin "4") (pinfunction "4_4") (pintype "passive"))
      (node (ref "C6") (pin "2") (pinfunction "2_2") (pintype "passive"))
      (node (ref "R_BOOT") (pin "1") (pinfunction "1_1") (pintype "passive"))
      (node (ref "U2") (pin "15") (pinfunction "IO9_15") (pintype "bidirectional"))
    )
    (net (code "18") (name "IO{slash}CHANGE") (class "Default")
      (node (ref "C10") (pin "2") (pinfunction "2_2") (pintype "passive"))
      (node (ref "CHANGE_BUTTON") (pin "3") (pinfunction "3_3") (pintype "passive"))
      (node (ref "CHANGE_BUTTON") (pin "4") (pinfunction "4_4") (pintype "passive"))
      (node (ref "R_CHANGE") (pin "1") (pinfunction "1_1") (pintype "passive"))
      (node (ref "U2") (pin "23") (pinfunction "IO15_23") (pintype "bidirectional"))
    )
    (net (code "19") (name "MISO") (class "Default")
      (node (ref "D12") (pin "2") (pinfunction "2_2") (pintype "passive"))
      (node (ref "J4") (pin "P7") (pinfunction "DAT0_P7") (pintype "bidirectional"))
      (node (ref "R8") (pin "1") (pinfunction "1_1") (pintype "passive"))
      (node (ref "TP6") (pin "TP") (pinfunction "TP_TP") (pintype "input"))
      (node (ref "U1") (pin "2") (pinfunction "DO(IO1)_2") (pintype "bidirectional"))
      (node (ref "U2") (pin "27") (pinfunction "IO2_27") (pintype "bidirectional"))
    )
    (net (code "20") (name "MOSI") (class "Default")
      (node (ref "D11") (pin "2") (pinfunction "2_2") (pintype "passive"))
      (node (ref "J1") (pin "14") (pinfunction "14_14") (pintype "bidirectional"))
      (node (ref "J4") (pin "P3") (pinfunction "CMD_P3") (pintype "bidirectional"))
      (node (ref "R7") (pin "1") (pinfunction "1_1") (pintype "passive"))
      (node (ref "TP7") (pin "TP") (pinfunction "TP_TP") (pintype "input"))
      (node (ref "U1") (pin "5") (pinfunction "DI(IO0)_5") (pintype "bidirectional"))
      (node (ref "U2") (pin "7") (pinfunction "IO7_7") (pintype "bidirectional"))
    )
    (net (code "21") (name "Net-(CHG_LED-PadC)") (class "Default")
      (node (ref "CHG_LED") (pin "C") (pinfunction "C_C") (pintype "passive"))
      (node (ref "R1_BAT") (pin "1") (pinfunction "1_1") (pintype "passive"))
    )
    (net (code "22") (name "Net-(D2-CATHODE)") (class "Default")
      (node (ref "C1_BAT1") (pin "2") (pinfunction "2_2") (pintype "passive"))
      (node (ref "D2") (pin "1") (pinfunction "CATHODE_1") (pintype "bidirectional"))
      (node (ref "IC4") (pin "1") (pinfunction "VIN_1") (pintype "bidirectional"))
      (node (ref "IC4") (pin "3") (pinfunction "CE_3") (pintype "bidirectional"))
      (node (ref "Q1") (pin "2") (pinfunction "S_2") (pintype "bidirectional"))
    )
    (net (code "23") (name "Net-(D3-A)") (class "Default")
      (node (ref "C4") (pin "2") (pinfunction "2_2") (pintype "passive"))
      (node (ref "D3") (pin "2") (pinfunction "A_2") (pintype "bidirectional"))
      (node (ref "D4") (pin "1") (pinfunction "K_1") (pintype "bidirectional"))
    )
    (net (code "24") (name "Net-(D7-CATHODE)") (class "Default")
      (node (ref "D7") (pin "1") (pinfunction "CATHODE_1") (pintype "bidirectional"))
      (node (ref "R_CAPACITOR") (pin "2") (pinfunction "2_2") (pintype "passive"))
    )
    (net (code "25") (name "Net-(EPD_C1-Pad1)") (class "Default")
      (node (ref "EPD_C1") (pin "1") (pinfunction "1_1") (pintype "passive"))
      (node (ref "J1") (pin "4") (pinfunction "4_4") (pintype "bidirectional"))
    )
    (net (code "26") (name "Net-(EPD_C2-Pad1)") (class "Default")
      (node (ref "EPD_C2") (pin "1") (pinfunction "1_1") (pintype "passive"))
      (node (ref "J1") (pin "5") (pinfunction "5_5") (pintype "bidirectional"))
    )
    (net (code "27") (name "Net-(EPD_C6-Pad1)") (class "Default")
      (node (ref "EPD_C6") (pin "1") (pinfunction "1_1") (pintype "passive"))
      (node (ref "J1") (pin "18") (pinfunction "18_18") (pintype "bidirectional"))
    )
    (net (code "28") (name "Net-(EPD_C7-Pad1)") (class "Default")
      (node (ref "EPD_C7") (pin "1") (pinfunction "1_1") (pintype "passive"))
      (node (ref "J1") (pin "19") (pinfunction "19_19") (pintype "bidirectional"))
    )
    (net (code "29") (name "Net-(EPD_C8-Pad1)") (class "Default")
      (node (ref "EPD_C8") (pin "1") (pinfunction "1_1") (pintype "passive"))
      (node (ref "J1") (pin "20") (pinfunction "20_20") (pintype "bidirectional"))
    )
    (net (code "30") (name "Net-(EPD_C10-Pad1)") (class "Default")
      (node (ref "EPD_C10") (pin "1") (pinfunction "1_1") (pintype "passive"))
      (node (ref "J1") (pin "22") (pinfunction "22_22") (pintype "bidirectional"))
    )
    (net (code "31") (name "Net-(EPD_C12-Pad1)") (class "Default")
      (node (ref "EPD_C12") (pin "1") (pinfunction "1_1") (pintype "passive"))
      (node (ref "J1") (pin "24") (pinfunction "24_24") (pintype "bidirectional"))
    )
    (net (code "32") (name "Net-(IC1-CT)") (class "Default")
      (node (ref "C_DELAY") (pin "2") (pinfunction "2_2") (pintype "passive"))
      (node (ref "IC1") (pin "5") (pinfunction "CT_5") (pintype "bidirectional"))
    )
    (net (code "33") (name "Net-(J2-PadA5)") (class "Default")
      (node (ref "J2") (pin "A5") (pinfunction "A5_A5") (pintype "bidirectional"))
      (node (ref "R2-USB1") (pin "2") (pinfunction "2_2") (pintype "passive"))
    )
    (net (code "34") (name "Net-(J2-PadB5)") (class "Default")
      (node (ref "J2") (pin "B5") (pinfunction "B5_B5") (pintype "bidirectional"))
      (node (ref "R2-USB") (pin "1") (pinfunction "1_1") (pintype "passive"))
    )
    (net (code "35") (name "Net-(MCP73831-PROG)") (class "Default")
      (node (ref "MCP73831") (pin "5") (pinfunction "PROG_5") (pintype "input"))
      (node (ref "R2_BAT") (pin "2") (pinfunction "2_2") (pintype "passive"))
    )
    (net (code "36") (name "Net-(MCP73831-STAT)") (class "Default")
      (node (ref "MCP73831") (pin "1") (pinfunction "STAT_1") (pintype "output"))
      (node (ref "R1_BAT") (pin "2") (pinfunction "2_2") (pintype "passive"))
    )
    (net (code "37") (name "PREVGH") (class "Default")
      (node (ref "D5") (pin "1") (pinfunction "K_1") (pintype "bidirectional"))
      (node (ref "EPD_C9") (pin "1") (pinfunction "1_1") (pintype "passive"))
      (node (ref "J1") (pin "21") (pinfunction "21_21") (pintype "bidirectional"))
    )
    (net (code "38") (name "PREVGL") (class "Default")
      (node (ref "D4") (pin "2") (pinfunction "A_2") (pintype "bidirectional"))
      (node (ref "EPD_C11") (pin "1") (pinfunction "1_1") (pintype "passive"))
      (node (ref "J1") (pin "23") (pinfunction "23_23") (pintype "bidirectional"))
    )
    (net (code "39") (name "RESE") (class "Default")
      (node (ref "J1") (pin "3") (pinfunction "3_3") (pintype "bidirectional"))
      (node (ref "Q3") (pin "2") (pinfunction "S_2") (pintype "bidirectional"))
      (node (ref "R3") (pin "2") (pinfunction "2_2") (pintype "passive"))
    )
    (net (code "40") (name "RESE'") (class "Default")
      (node (ref "R2") (pin "2") (pinfunction "2_2") (pintype "passive"))
      (node (ref "R3") (pin "1") (pinfunction "1_1") (pintype "passive"))
      (node (ref "SJ1") (pin "2") (pinfunction "2_2") (pintype "passive"))
    )
    (net (code "41") (name "RESET") (class "Default")
      (node (ref "C5") (pin "2") (pinfunction "2_2") (pintype "passive"))
      (node (ref "IC1") (pin "1") (pinfunction "VOUT_1") (pintype "bidirectional"))
      (node (ref "RESET_BUTTON") (pin "3") (pinfunction "3_3") (pintype "passive"))
      (node (ref "RESET_BUTTON") (pin "4") (pinfunction "4_4") (pintype "passive"))
      (node (ref "R_RESET") (pin "1") (pinfunction "1_1") (pintype "passive"))
      (node (ref "U2") (pin "3") (pinfunction "EN_3") (pintype "input"))
    )
    (net (code "42") (name "RTC_RST") (class "Default")
      (node (ref "U2") (pin "16") (pinfunction "IO18_16") (pintype "bidirectional"))
      (node (ref "U3") (pin "4") (pinfunction "~{RST}_4") (pintype "input"))
    )
    (net (code "43") (name "RX") (class "Default")
      (node (ref "TP2") (pin "TP") (pinfunction "TP_TP") (pintype "input"))
      (node (ref "U2") (pin "24") (pinfunction "RXD0/GPIO17_24") (pintype "bidirectional"))
    )
    (net (code "44") (name "SCK") (class "Default")
      (node (ref "D10") (pin "2") (pinfunction "2_2") (pintype "passive"))
      (node (ref "J1") (pin "13") (pinfunction "13_13") (pintype "bidirectional"))
      (node (ref "J4") (pin "P5") (pinfunction "CLK_P5") (pintype "bidirectional"))
      (node (ref "R6") (pin "1") (pinfunction "1_1") (pintype "passive"))
      (node (ref "TP8") (pin "TP") (pinfunction "TP_TP") (pintype "input"))
      (node (ref "U1") (pin "6") (pinfunction "CLK_6") (pintype "input"))
      (node (ref "U2") (pin "6") (pinfunction "IO6_6") (pintype "bidirectional"))
    )
    (net (code "45") (name "SCL") (class "Default")
      (node (ref "J3") (pin "4") (pinfunction "4_4") (pintype "passive"))
      (node (ref "R2-PINH") (pin "1") (pinfunction "1_1") (pintype "passive"))
      (node (ref "SENSOR2") (pin "4") (pinfunction "SCK_4") (pintype "input"))
      (node (ref "U2") (pin "20") (pinfunction "IO22_20") (pintype "bidirectional"))
      (node (ref "U3") (pin "16") (pinfunction "SCL_16") (pintype "input"))
      (node (ref "U4") (pin "7") (pinfunction "SCL_7") (pintype "input"))
    )
    (net (code "46") (name "SDA") (class "Default")
      (node (ref "J3") (pin "3") (pinfunction "3_3") (pintype "passive"))
      (node (ref "R1_PINH") (pin "1") (pinfunction "1_1") (pintype "passive"))
      (node (ref "SENSOR2") (pin "3") (pinfunction "SDI_3") (pintype "bidirectional"))
      (node (ref "U2") (pin "19") (pinfunction "IO21_19") (pintype "bidirectional"))
      (node (ref "U3") (pin "15") (pinfunction "SDA_15") (pintype "bidirectional"))
      (node (ref "U4") (pin "8") (pinfunction "SDA_8") (pintype "bidirectional"))
    )
    (net (code "47") (name "SRC") (class "Default")
      (node (ref "C4") (pin "1") (pinfunction "1_1") (pintype "passive"))
      (node (ref "D5") (pin "2") (pinfunction "A_2") (pintype "bidirectional"))
      (node (ref "L1") (pin "1") (pinfunction "1_1") (pintype "passive"))
      (node (ref "Q3") (pin "3") (pinfunction "D_3") (pintype "bidirectional"))
    )
    (net (code "48") (name "SS_SD") (class "Default")
      (node (ref "D8") (pin "2") (pinfunction "2_2") (pintype "passive"))
      (node (ref "J4") (pin "P2") (pinfunction "CD/DAT3_P2") (pintype "bidirectional"))
      (node (ref "R10") (pin "1") (pinfunction "1_1") (pintype "passive"))
      (node (ref "U2") (pin "4") (pinfunction "IO4_4") (pintype "bidirectional"))
    )
    (net (code "49") (name "TX") (class "Default")
      (node (ref "TP1") (pin "TP") (pinfunction "TP_TP") (pintype "input"))
      (node (ref "U2") (pin "25") (pinfunction "TXD0/GPIO16_25") (pintype "bidirectional"))
    )
    (net (code "50") (name "USB_D+") (class "Default")
      (node (ref "D1") (pin "1") (pinfunction "I/O1_1_1") (pintype "bidirectional"))
      (node (ref "U2") (pin "14") (pinfunction "IO13_14") (pintype "bidirectional"))
    )
    (net (code "51") (name "USB_D-") (class "Default")
      (node (ref "D1") (pin "3") (pinfunction "I/O2_1_3") (pintype "bidirectional"))
      (node (ref "U2") (pin "13") (pinfunction "IO12_13") (pintype "bidirectional"))
    )
    (net (code "52") (name "VBAT") (class "Default")
      (node (ref "C2_BAT") (pin "2") (pinfunction "2_2") (pintype "passive"))
      (node (ref "MCP73831") (pin "3") (pinfunction "VBAT_3") (pintype "power_in"))
      (node (ref "Q1") (pin "3") (pinfunction "D_3") (pintype "bidirectional"))
      (node (ref "TP3") (pin "TP") (pinfunction "TP_TP") (pintype "input"))
      (node (ref "U4") (pin "2") (pinfunction "CELL_2") (pintype "power_in"))
      (node (ref "U4") (pin "3") (pinfunction "VDD_3") (pintype "power_in"))
    )
    (net (code "53") (name "VBUS") (class "Default")
      (node (ref "C1_BAT") (pin "2") (pinfunction "2_2") (pintype "passive"))
      (node (ref "C4_USB") (pin "2") (pinfunction "2_2") (pintype "passive"))
      (node (ref "C5_USB") (pin "2") (pinfunction "2_2") (pintype "passive"))
      (node (ref "CHG_LED") (pin "A") (pinfunction "A_A") (pintype "passive"))
      (node (ref "D1") (pin "5") (pinfunction "VBUS_5") (pintype "bidirectional"))
      (node (ref "D2") (pin "2") (pinfunction "ANODE_2") (pintype "bidirectional"))
      (node (ref "MCP73831") (pin "4") (pinfunction "VIN_4") (pintype "power_in"))
      (node (ref "PFMF.050.1") (pin "2") (pinfunction "2_2") (pintype "passive"))
      (node (ref "Q1") (pin "1") (pinfunction "G_1") (pintype "bidirectional"))
      (node (ref "R1_PWRUSB") (pin "1") (pinfunction "1_1") (pintype "passive"))
      (node (ref "TP14") (pin "TP") (pinfunction "TP_TP") (pintype "input"))
    )
    (net (code "54") (name "VRTC") (class "Default")
      (node (ref "C10_SUPERCAP") (pin "2") (pinfunction "2_2") (pintype "passive"))
      (node (ref "C8") (pin "1") (pinfunction "1_1") (pintype "passive"))
      (node (ref "R_CAPACITOR") (pin "1") (pinfunction "1_1") (pintype "passive"))
      (node (ref "U3") (pin "14") (pinfunction "VBAT_14") (pintype "power_in"))
    )
    (net (code "55") (name "VUSB") (class "Default")
      (node (ref "J2") (pin "A4") (pinfunction "A4_A4") (pintype "bidirectional"))
      (node (ref "J2") (pin "A9") (pinfunction "A9_A9") (pintype "bidirectional"))
      (node (ref "J2") (pin "B4") (pinfunction "B4_B4") (pintype "bidirectional"))
      (node (ref "J2") (pin "B9") (pinfunction "B9_B9") (pintype "bidirectional"))
      (node (ref "PFMF.050.1") (pin "1") (pinfunction "1_1") (pintype "passive"))
    )
    (net (code "56") (name "unconnected-(IC1-NC-Pad4)") (class "Default")
      (node (ref "IC1") (pin "4") (pinfunction "NC_4") (pintype "no_connect"))
    )
    (net (code "57") (name "unconnected-(IC4-NC-Pad4)") (class "Default")
      (node (ref "IC4") (pin "4") (pinfunction "NC_4") (pintype "no_connect"))
    )
    (net (code "58") (name "unconnected-(J1-Pad1)") (class "Default")
      (node (ref "J1") (pin "1") (pinfunction "1_1") (pintype "bidirectional"))
    )
    (net (code "59") (name "unconnected-(J1-Pad6)") (class "Default")
      (node (ref "J1") (pin "6") (pinfunction "6_6") (pintype "bidirectional"))
    )
    (net (code "60") (name "unconnected-(J1-Pad7)") (class "Default")
      (node (ref "J1") (pin "7") (pinfunction "7_7") (pintype "bidirectional"))
    )
    (net (code "61") (name "unconnected-(J2-PadA8)") (class "Default")
      (node (ref "J2") (pin "A8") (pinfunction "A8_A8") (pintype "bidirectional"))
    )
    (net (code "62") (name "unconnected-(J2-PadB8)") (class "Default")
      (node (ref "J2") (pin "B8") (pinfunction "B8_B8") (pintype "bidirectional"))
    )
    (net (code "63") (name "unconnected-(J4-DAT1-PadP8)") (class "Default")
      (node (ref "J4") (pin "P8") (pinfunction "DAT1_P8") (pintype "bidirectional"))
    )
    (net (code "64") (name "unconnected-(J4-DAT2-PadP1)") (class "Default")
      (node (ref "J4") (pin "P1") (pinfunction "DAT2_P1") (pintype "bidirectional"))
    )
    (net (code "65") (name "unconnected-(J4-DETECTION_1-PadS1)") (class "Default")
      (node (ref "J4") (pin "S1") (pinfunction "DETECTION_1_S1") (pintype "bidirectional"))
    )
    (net (code "66") (name "unconnected-(J4-DETECTION_2-PadS2)") (class "Default")
      (node (ref "J4") (pin "S2") (pinfunction "DETECTION_2_S2") (pintype "bidirectional"))
    )
    (net (code "67") (name "unconnected-(U2-NC-Pad22)") (class "Default")
      (node (ref "U2") (pin "22") (pinfunction "NC_22") (pintype "no_connect"))
    )
    (net (code "68") (name "unconnected-(U4-~{ALERT}-Pad5)") (class "Default")
      (node (ref "U4") (pin "5") (pinfunction "~{ALERT}_5") (pintype "output"))
    )
  )
)
